# eskeetit.net
KiCad netlist of a schematic drawn in EAGLE
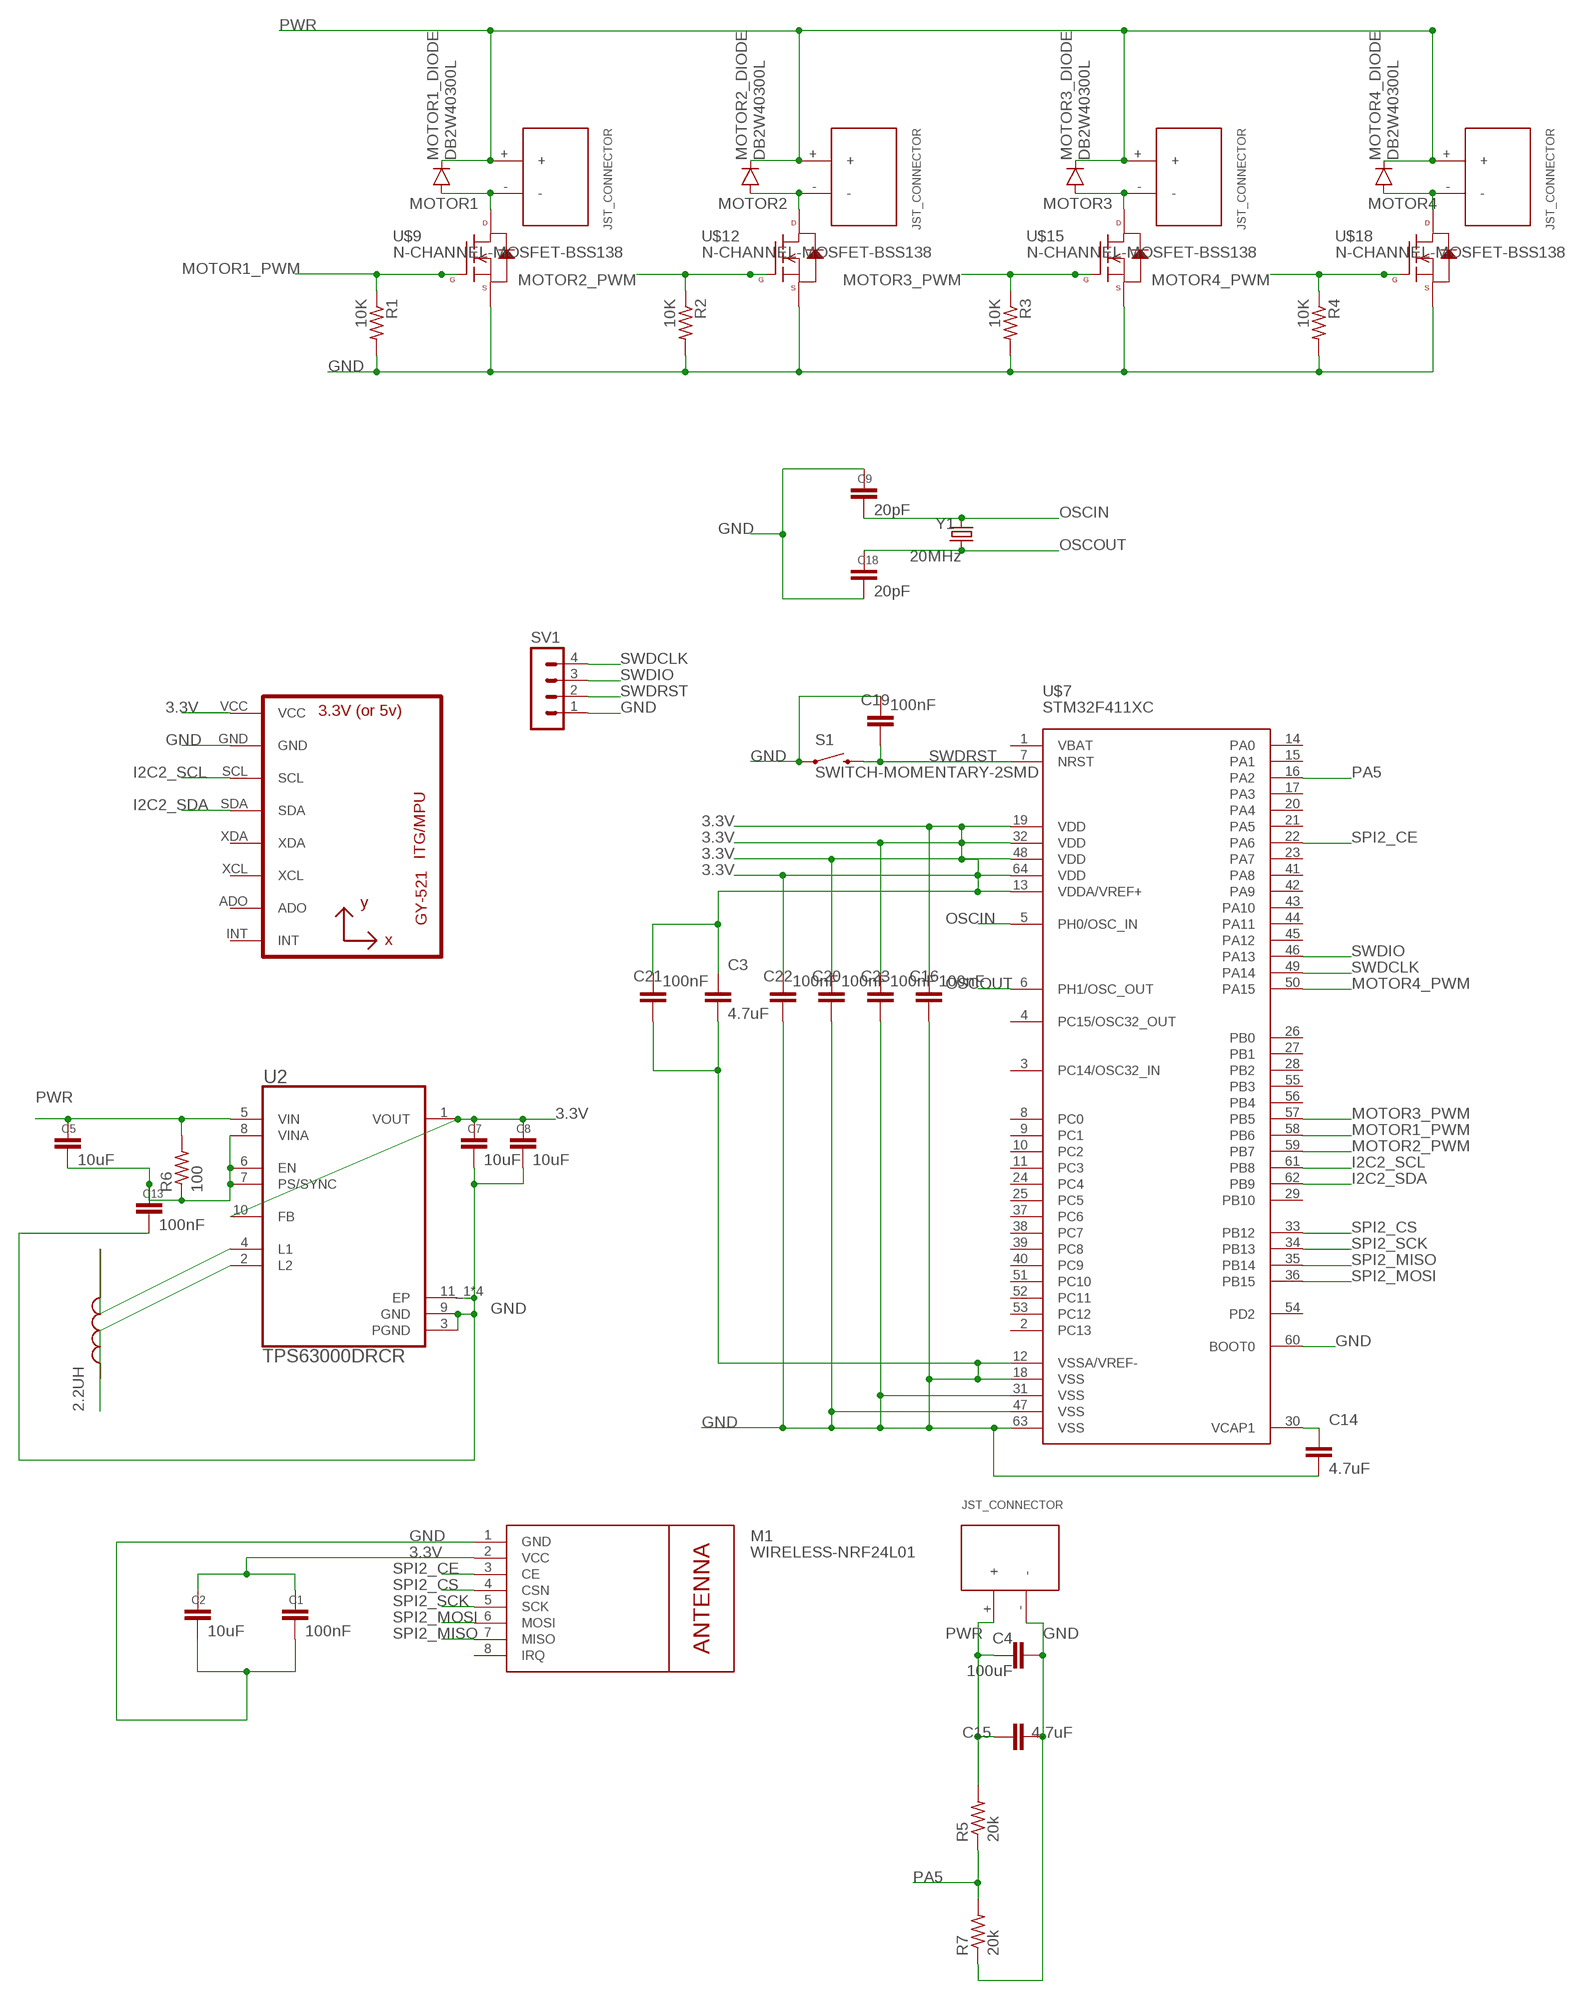
[diagram p0: schematic, sheet 1]

(export (version "E")
  (design (tool "Eeschema 10.0.6"))
  (components
    (comp (ref "2.2UH")
      (value "2.2uH")
      (footprint "eagle-import:IND_LQH2MCN100K02L")
      (fields
        (field (name "DIGI-KEY_PART_NUMBER") "490-4046-1-ND")
        (field (name "MF") "Murata Electronics")
        (field (name "MP") "LQH2MCN100K02L")
      )
      (libsource (lib "eagle-import") (part "LQH2MCN100K02L"))
    )
    (comp (ref "C1")
      (value "100nF")
      (footprint "eagle-import:RCL_C0603")
      (libsource (lib "eagle-import") (part "RCL_C-EUC0603"))
    )
    (comp (ref "C2")
      (value "10uF")
      (footprint "eagle-import:RCL_C0603")
      (libsource (lib "eagle-import") (part "RCL_C-EUC0603"))
    )
    (comp (ref "C3")
      (value "4.7uF")
      (footprint "eagle-import:RCL_C0603")
      (libsource (lib "eagle-import") (part "RCL_C-EUC0603"))
    )
    (comp (ref "C4")
      (value "100uF")
      (footprint "eagle-import:C1206")
      (libsource (lib "eagle-import") (part "C-EUC1206"))
    )
    (comp (ref "C5")
      (value "10uF")
      (footprint "eagle-import:RCL_C0603")
      (libsource (lib "eagle-import") (part "RCL_C-EUC0603"))
    )
    (comp (ref "C7")
      (value "10uF")
      (footprint "eagle-import:RCL_C0603")
      (libsource (lib "eagle-import") (part "RCL_C-EUC0603"))
    )
    (comp (ref "C8")
      (value "10uF")
      (footprint "eagle-import:RCL_C0603")
      (libsource (lib "eagle-import") (part "RCL_C-EUC0603"))
    )
    (comp (ref "C9")
      (value "20pF")
      (footprint "eagle-import:RCL_C0603")
      (libsource (lib "eagle-import") (part "RCL_C-EUC0603"))
    )
    (comp (ref "C13")
      (value "100nF")
      (footprint "eagle-import:RCL_C0603")
      (libsource (lib "eagle-import") (part "RCL_C-EUC0603"))
    )
    (comp (ref "C14")
      (value "4.7uF")
      (footprint "eagle-import:RCL_C0603")
      (libsource (lib "eagle-import") (part "RCL_C-EUC0603"))
    )
    (comp (ref "C15")
      (value "4.7uF")
      (footprint "eagle-import:RCL_C0603")
      (libsource (lib "eagle-import") (part "RCL_C-EUC0603"))
    )
    (comp (ref "C16")
      (value "100nF")
      (footprint "eagle-import:RCL_C0603")
      (libsource (lib "eagle-import") (part "RCL_C-EUC0603"))
    )
    (comp (ref "C18")
      (value "20pF")
      (footprint "eagle-import:RCL_C0603")
      (libsource (lib "eagle-import") (part "RCL_C-EUC0603"))
    )
    (comp (ref "C19")
      (value "100nF")
      (footprint "eagle-import:RCL_C0603")
      (libsource (lib "eagle-import") (part "RCL_C-EUC0603"))
    )
    (comp (ref "C20")
      (value "100nF")
      (footprint "eagle-import:RCL_C0603")
      (libsource (lib "eagle-import") (part "RCL_C-EUC0603"))
    )
    (comp (ref "C21")
      (value "100nF")
      (footprint "eagle-import:RCL_C0603")
      (libsource (lib "eagle-import") (part "RCL_C-EUC0603"))
    )
    (comp (ref "C22")
      (value "100nF")
      (footprint "eagle-import:RCL_C0603")
      (libsource (lib "eagle-import") (part "RCL_C-EUC0603"))
    )
    (comp (ref "C23")
      (value "100nF")
      (footprint "eagle-import:RCL_C0603")
      (libsource (lib "eagle-import") (part "RCL_C-EUC0603"))
    )
    (comp (ref "M1")
      (value "WIRELESS-NRF24L01")
      (footprint "eagle-import:WIRELESS-NRF24L01")
      (libsource (lib "eagle-import") (part "WIRELESS-NRF24L01"))
    )
    (comp (ref "MOTOR1")
      (value "JST_CONNECTOR_FEMALE")
      (footprint "eagle-import:JST_CONNECTOR_FEMALE")
      (libsource (lib "eagle-import") (part "JST_CONNECTOR_FEMALE"))
    )
    (comp (ref "MOTOR1_DIODE")
      (value "DB2W40300L")
      (footprint "eagle-import:MINI2-F3-B")
      (libsource (lib "eagle-import") (part "DB2W40300L"))
    )
    (comp (ref "MOTOR2_DIODE")
      (value "DB2W40300L")
      (footprint "eagle-import:MINI2-F3-B")
      (libsource (lib "eagle-import") (part "DB2W40300L"))
    )
    (comp (ref "MOTOR3_DIODE")
      (value "DB2W40300L")
      (footprint "eagle-import:MINI2-F3-B")
      (libsource (lib "eagle-import") (part "DB2W40300L"))
    )
    (comp (ref "MOTOR4_DIODE")
      (value "DB2W40300L")
      (footprint "eagle-import:MINI2-F3-B")
      (libsource (lib "eagle-import") (part "DB2W40300L"))
    )
    (comp (ref "R1")
      (value "10K")
      (footprint "eagle-import:R0603")
      (libsource (lib "eagle-import") (part "R-US_R0603"))
    )
    (comp (ref "R2")
      (value "10K")
      (footprint "eagle-import:R0603")
      (libsource (lib "eagle-import") (part "R-US_R0603"))
    )
    (comp (ref "R3")
      (value "10K")
      (footprint "eagle-import:R0603")
      (libsource (lib "eagle-import") (part "R-US_R0603"))
    )
    (comp (ref "R4")
      (value "10K")
      (footprint "eagle-import:R0603")
      (libsource (lib "eagle-import") (part "R-US_R0603"))
    )
    (comp (ref "R5")
      (value "20k")
      (footprint "eagle-import:R0603")
      (libsource (lib "eagle-import") (part "R-US_R0603"))
    )
    (comp (ref "R6")
      (value "100")
      (footprint "eagle-import:R0603")
      (libsource (lib "eagle-import") (part "R-US_R0603"))
    )
    (comp (ref "R7")
      (value "20k")
      (footprint "eagle-import:R0603")
      (libsource (lib "eagle-import") (part "R-US_R0603"))
    )
    (comp (ref "S1")
      (value "SWITCH-MOMENTARY-2SMD")
      (footprint "eagle-import:TACTILE-SWITCH-SMD")
      (libsource (lib "eagle-import") (part "SWITCH-MOMENTARY-2SMD"))
    )
    (comp (ref "SV1")
      (value "MA04-1")
      (footprint "eagle-import:MA04-1")
      (libsource (lib "eagle-import") (part "MA04-1"))
    )
    (comp (ref "U$1")
      (value "JST_CONNECTOR_FEMALE")
      (footprint "eagle-import:JST_CONNECTOR_FEMALE")
      (libsource (lib "eagle-import") (part "JST_CONNECTOR_FEMALE"))
    )
    (comp (ref "U$7")
      (value "STM32F411XC")
      (footprint "eagle-import:LQFP64")
      (libsource (lib "eagle-import") (part "STM32F411XC"))
    )
    (comp (ref "U$9")
      (value "N-CHANNEL-MOSFET-BSS138")
      (footprint "eagle-import:SOT23-3")
      (libsource (lib "eagle-import") (part "N-CHANNEL-MOSFET-BSS138"))
    )
    (comp (ref "U$11")
      (value "JST_CONNECTOR_FEMALE")
      (footprint "eagle-import:JST_CONNECTOR_FEMALE")
      (libsource (lib "eagle-import") (part "JST_CONNECTOR_FEMALE"))
    )
    (comp (ref "U$12")
      (value "N-CHANNEL-MOSFET-BSS138")
      (footprint "eagle-import:SOT23-3")
      (libsource (lib "eagle-import") (part "N-CHANNEL-MOSFET-BSS138"))
    )
    (comp (ref "U$14")
      (value "JST_CONNECTOR_FEMALE")
      (footprint "eagle-import:JST_CONNECTOR_FEMALE")
      (libsource (lib "eagle-import") (part "JST_CONNECTOR_FEMALE"))
    )
    (comp (ref "U$15")
      (value "N-CHANNEL-MOSFET-BSS138")
      (footprint "eagle-import:SOT23-3")
      (libsource (lib "eagle-import") (part "N-CHANNEL-MOSFET-BSS138"))
    )
    (comp (ref "U$17")
      (value "JST_CONNECTOR_FEMALE")
      (footprint "eagle-import:JST_CONNECTOR_FEMALE")
      (libsource (lib "eagle-import") (part "JST_CONNECTOR_FEMALE"))
    )
    (comp (ref "U$18")
      (value "N-CHANNEL-MOSFET-BSS138")
      (footprint "eagle-import:SOT23-3")
      (libsource (lib "eagle-import") (part "N-CHANNEL-MOSFET-BSS138"))
    )
    (comp (ref "U1")
      (value "GY-521MPU6050")
      (footprint "eagle-import:GY-521")
      (libsource (lib "eagle-import") (part "GY-521MPU6050"))
    )
    (comp (ref "U2")
      (value "TPS63000DRCR")
      (footprint "eagle-import:CONV_TPS63000DRCR")
      (fields (field (name "DIGI-KEY_PART_NUMBER") "296-19641-1-ND") (field (name "MF") "Texas Instruments"))
      (libsource (lib "eagle-import") (part "TPS63000DRCR"))
    )
    (comp (ref "Y1")
      (value "20MHz")
      (footprint "eagle-import:HC49US")
      (libsource (lib "eagle-import") (part "CRYSTALHC49US"))
    )
  )
  (nets
    (net (code "1") (name "/3.3V") (class "Default")
      (node (ref "C1") (pin "1") (pinfunction "1_1") (pintype "passive"))
      (node (ref "C16") (pin "1") (pinfunction "1_1") (pintype "passive"))
      (node (ref "C2") (pin "1") (pinfunction "1_1") (pintype "passive"))
      (node (ref "C20") (pin "1") (pinfunction "1_1") (pintype "passive"))
      (node (ref "C21") (pin "1") (pinfunction "1_1") (pintype "passive"))
      (node (ref "C22") (pin "1") (pinfunction "1_1") (pintype "passive"))
      (node (ref "C23") (pin "1") (pinfunction "1_1") (pintype "passive"))
      (node (ref "C3") (pin "1") (pinfunction "1_1") (pintype "passive"))
      (node (ref "C7") (pin "1") (pinfunction "1_1") (pintype "passive"))
      (node (ref "C8") (pin "1") (pinfunction "1_1") (pintype "passive"))
      (node (ref "M1") (pin "2") (pinfunction "VCC_2") (pintype "power_in"))
      (node (ref "U$7") (pin "13") (pinfunction "VDDA/VREF+_13") (pintype "bidirectional"))
      (node (ref "U$7") (pin "19") (pinfunction "VDD_19") (pintype "bidirectional"))
      (node (ref "U$7") (pin "32") (pinfunction "VDD_32") (pintype "bidirectional"))
      (node (ref "U$7") (pin "48") (pinfunction "VDD_48") (pintype "bidirectional"))
      (node (ref "U$7") (pin "64") (pinfunction "VDD_64") (pintype "bidirectional"))
      (node (ref "U1") (pin "VCC") (pinfunction "VCC_VCC") (pintype "bidirectional"))
      (node (ref "U2") (pin "1") (pinfunction "VOUT_1") (pintype "output"))
      (node (ref "U2") (pin "10") (pinfunction "FB_10") (pintype "input"))
    )
    (net (code "2") (name "/GND") (class "Default")
      (node (ref "C1") (pin "2") (pinfunction "2_2") (pintype "passive"))
      (node (ref "C13") (pin "2") (pinfunction "2_2") (pintype "passive"))
      (node (ref "C14") (pin "2") (pinfunction "2_2") (pintype "passive"))
      (node (ref "C15") (pin "2") (pinfunction "2_2") (pintype "passive"))
      (node (ref "C16") (pin "2") (pinfunction "2_2") (pintype "passive"))
      (node (ref "C18") (pin "2") (pinfunction "2_2") (pintype "passive"))
      (node (ref "C19") (pin "1") (pinfunction "1_1") (pintype "passive"))
      (node (ref "C2") (pin "2") (pinfunction "2_2") (pintype "passive"))
      (node (ref "C20") (pin "2") (pinfunction "2_2") (pintype "passive"))
      (node (ref "C21") (pin "2") (pinfunction "2_2") (pintype "passive"))
      (node (ref "C22") (pin "2") (pinfunction "2_2") (pintype "passive"))
      (node (ref "C23") (pin "2") (pinfunction "2_2") (pintype "passive"))
      (node (ref "C3") (pin "2") (pinfunction "2_2") (pintype "passive"))
      (node (ref "C4") (pin "1") (pinfunction "1_1") (pintype "passive"))
      (node (ref "C7") (pin "2") (pinfunction "2_2") (pintype "passive"))
      (node (ref "C8") (pin "2") (pinfunction "2_2") (pintype "passive"))
      (node (ref "C9") (pin "1") (pinfunction "1_1") (pintype "passive"))
      (node (ref "M1") (pin "1") (pinfunction "GND_1") (pintype "power_in"))
      (node (ref "R1") (pin "2") (pinfunction "2_2") (pintype "passive"))
      (node (ref "R2") (pin "2") (pinfunction "2_2") (pintype "passive"))
      (node (ref "R3") (pin "2") (pinfunction "2_2") (pintype "passive"))
      (node (ref "R4") (pin "2") (pinfunction "2_2") (pintype "passive"))
      (node (ref "R7") (pin "1") (pinfunction "1_1") (pintype "passive"))
      (node (ref "S1") (pin "1") (pinfunction "1_1") (pintype "passive"))
      (node (ref "SV1") (pin "1") (pinfunction "1_1") (pintype "passive"))
      (node (ref "U$1") (pin "-") (pinfunction "-_-") (pintype "bidirectional"))
      (node (ref "U$12") (pin "2") (pinfunction "S_2") (pintype "passive"))
      (node (ref "U$15") (pin "2") (pinfunction "S_2") (pintype "passive"))
      (node (ref "U$18") (pin "2") (pinfunction "S_2") (pintype "passive"))
      (node (ref "U$7") (pin "12") (pinfunction "VSSA/VREF-_12") (pintype "bidirectional"))
      (node (ref "U$7") (pin "18") (pinfunction "VSS_18") (pintype "bidirectional"))
      (node (ref "U$7") (pin "31") (pinfunction "VSS_31") (pintype "bidirectional"))
      (node (ref "U$7") (pin "47") (pinfunction "VSS_47") (pintype "bidirectional"))
      (node (ref "U$7") (pin "60") (pinfunction "BOOT0_60") (pintype "bidirectional"))
      (node (ref "U$7") (pin "63") (pinfunction "VSS_63") (pintype "bidirectional"))
      (node (ref "U$9") (pin "2") (pinfunction "S_2") (pintype "passive"))
      (node (ref "U1") (pin "GND") (pinfunction "GND_GND") (pintype "bidirectional"))
      (node (ref "U2") (pin "11_1") (pinfunction "EP_11_1") (pintype "power_in"))
      (node (ref "U2") (pin "11_2") (pinfunction "EP_11_2") (pintype "power_in"))
      (node (ref "U2") (pin "11_3") (pinfunction "EP_11_3") (pintype "power_in"))
      (node (ref "U2") (pin "11_4") (pinfunction "EP_11_4") (pintype "power_in"))
      (node (ref "U2") (pin "3") (pinfunction "PGND_3") (pintype "power_in"))
      (node (ref "U2") (pin "9") (pinfunction "GND_9") (pintype "power_in"))
    )
    (net (code "3") (name "/I2C2_SCL") (class "Default")
      (node (ref "U$7") (pin "61") (pinfunction "PB8_61") (pintype "bidirectional"))
      (node (ref "U1") (pin "SCL") (pinfunction "SCL_SCL") (pintype "bidirectional"))
    )
    (net (code "4") (name "/I2C2_SDA") (class "Default")
      (node (ref "U$7") (pin "62") (pinfunction "PB9_62") (pintype "bidirectional"))
      (node (ref "U1") (pin "SDA") (pinfunction "SDA_SDA") (pintype "bidirectional"))
    )
    (net (code "5") (name "/MOTOR1") (class "Default")
      (node (ref "MOTOR1") (pin "-") (pinfunction "-_-") (pintype "bidirectional"))
      (node (ref "MOTOR1_DIODE") (pin "POS") (pinfunction "PPIN_POS") (pintype "passive"))
      (node (ref "U$9") (pin "3") (pinfunction "D_3") (pintype "passive"))
    )
    (net (code "6") (name "/MOTOR1_PWM") (class "Default")
      (node (ref "R1") (pin "1") (pinfunction "1_1") (pintype "passive"))
      (node (ref "U$7") (pin "58") (pinfunction "PB6_58") (pintype "bidirectional"))
      (node (ref "U$9") (pin "1") (pinfunction "G_1") (pintype "passive"))
    )
    (net (code "7") (name "/MOTOR2") (class "Default")
      (node (ref "MOTOR2_DIODE") (pin "POS") (pinfunction "PPIN_POS") (pintype "passive"))
      (node (ref "U$11") (pin "-") (pinfunction "-_-") (pintype "bidirectional"))
      (node (ref "U$12") (pin "3") (pinfunction "D_3") (pintype "passive"))
    )
    (net (code "8") (name "/MOTOR2_PWM") (class "Default")
      (node (ref "R2") (pin "1") (pinfunction "1_1") (pintype "passive"))
      (node (ref "U$12") (pin "1") (pinfunction "G_1") (pintype "passive"))
      (node (ref "U$7") (pin "59") (pinfunction "PB7_59") (pintype "bidirectional"))
    )
    (net (code "9") (name "/MOTOR3") (class "Default")
      (node (ref "MOTOR3_DIODE") (pin "POS") (pinfunction "PPIN_POS") (pintype "passive"))
      (node (ref "U$14") (pin "-") (pinfunction "-_-") (pintype "bidirectional"))
      (node (ref "U$15") (pin "3") (pinfunction "D_3") (pintype "passive"))
    )
    (net (code "10") (name "/MOTOR3_PWM") (class "Default")
      (node (ref "R3") (pin "1") (pinfunction "1_1") (pintype "passive"))
      (node (ref "U$15") (pin "1") (pinfunction "G_1") (pintype "passive"))
      (node (ref "U$7") (pin "57") (pinfunction "PB5_57") (pintype "bidirectional"))
    )
    (net (code "11") (name "/MOTOR4") (class "Default")
      (node (ref "MOTOR4_DIODE") (pin "POS") (pinfunction "PPIN_POS") (pintype "passive"))
      (node (ref "U$17") (pin "-") (pinfunction "-_-") (pintype "bidirectional"))
      (node (ref "U$18") (pin "3") (pinfunction "D_3") (pintype "passive"))
    )
    (net (code "12") (name "/MOTOR4_PWM") (class "Default")
      (node (ref "R4") (pin "1") (pinfunction "1_1") (pintype "passive"))
      (node (ref "U$18") (pin "1") (pinfunction "G_1") (pintype "passive"))
      (node (ref "U$7") (pin "50") (pinfunction "PA15_50") (pintype "bidirectional"))
    )
    (net (code "13") (name "/OSCIN") (class "Default")
      (node (ref "C9") (pin "2") (pinfunction "2_2") (pintype "passive"))
      (node (ref "U$7") (pin "5") (pinfunction "PH0/OSC_IN_5") (pintype "bidirectional"))
      (node (ref "Y1") (pin "2") (pinfunction "2_2") (pintype "passive"))
    )
    (net (code "14") (name "/OSCOUT") (class "Default")
      (node (ref "C18") (pin "1") (pinfunction "1_1") (pintype "passive"))
      (node (ref "U$7") (pin "6") (pinfunction "PH1/OSC_OUT_6") (pintype "bidirectional"))
      (node (ref "Y1") (pin "1") (pinfunction "1_1") (pintype "passive"))
    )
    (net (code "15") (name "/PA5") (class "Default")
      (node (ref "R5") (pin "1") (pinfunction "1_1") (pintype "passive"))
      (node (ref "R7") (pin "2") (pinfunction "2_2") (pintype "passive"))
      (node (ref "U$7") (pin "16") (pinfunction "PA2_16") (pintype "bidirectional"))
    )
    (net (code "16") (name "/PWR") (class "Default")
      (node (ref "C15") (pin "1") (pinfunction "1_1") (pintype "passive"))
      (node (ref "C4") (pin "2") (pinfunction "2_2") (pintype "passive"))
      (node (ref "C5") (pin "1") (pinfunction "1_1") (pintype "passive"))
      (node (ref "MOTOR1") (pin "+") (pinfunction "+_+") (pintype "bidirectional"))
      (node (ref "MOTOR1_DIODE") (pin "NEG") (pinfunction "GPIN_NEG") (pintype "passive"))
      (node (ref "MOTOR2_DIODE") (pin "NEG") (pinfunction "GPIN_NEG") (pintype "passive"))
      (node (ref "MOTOR3_DIODE") (pin "NEG") (pinfunction "GPIN_NEG") (pintype "passive"))
      (node (ref "MOTOR4_DIODE") (pin "NEG") (pinfunction "GPIN_NEG") (pintype "passive"))
      (node (ref "R5") (pin "2") (pinfunction "2_2") (pintype "passive"))
      (node (ref "R6") (pin "2") (pinfunction "2_2") (pintype "passive"))
      (node (ref "U$1") (pin "+") (pinfunction "+_+") (pintype "bidirectional"))
      (node (ref "U$11") (pin "+") (pinfunction "+_+") (pintype "bidirectional"))
      (node (ref "U$14") (pin "+") (pinfunction "+_+") (pintype "bidirectional"))
      (node (ref "U$17") (pin "+") (pinfunction "+_+") (pintype "bidirectional"))
      (node (ref "U2") (pin "5") (pinfunction "VIN_5") (pintype "input"))
    )
    (net (code "17") (name "/SPI2_CE") (class "Default")
      (node (ref "M1") (pin "3") (pinfunction "CE_3") (pintype "bidirectional"))
      (node (ref "U$7") (pin "22") (pinfunction "PA6_22") (pintype "bidirectional"))
    )
    (net (code "18") (name "/SPI2_CS") (class "Default")
      (node (ref "M1") (pin "4") (pinfunction "CSN_4") (pintype "bidirectional"))
      (node (ref "U$7") (pin "33") (pinfunction "PB12_33") (pintype "bidirectional"))
    )
    (net (code "19") (name "/SPI2_MISO") (class "Default")
      (node (ref "M1") (pin "7") (pinfunction "MISO_7") (pintype "bidirectional"))
      (node (ref "U$7") (pin "35") (pinfunction "PB14_35") (pintype "bidirectional"))
    )
    (net (code "20") (name "/SPI2_MOSI") (class "Default")
      (node (ref "M1") (pin "6") (pinfunction "MOSI_6") (pintype "bidirectional"))
      (node (ref "U$7") (pin "36") (pinfunction "PB15_36") (pintype "bidirectional"))
    )
    (net (code "21") (name "/SPI2_SCK") (class "Default")
      (node (ref "M1") (pin "5") (pinfunction "SCK_5") (pintype "bidirectional"))
      (node (ref "U$7") (pin "34") (pinfunction "PB13_34") (pintype "bidirectional"))
    )
    (net (code "22") (name "/SWDCLK") (class "Default")
      (node (ref "SV1") (pin "4") (pinfunction "4_4") (pintype "passive"))
      (node (ref "U$7") (pin "49") (pinfunction "PA14_49") (pintype "bidirectional"))
    )
    (net (code "23") (name "/SWDIO") (class "Default")
      (node (ref "SV1") (pin "3") (pinfunction "3_3") (pintype "passive"))
      (node (ref "U$7") (pin "46") (pinfunction "PA13_46") (pintype "bidirectional"))
    )
    (net (code "24") (name "/SWDRST") (class "Default")
      (node (ref "C19") (pin "2") (pinfunction "2_2") (pintype "passive"))
      (node (ref "S1") (pin "3") (pinfunction "2_3") (pintype "passive"))
      (node (ref "SV1") (pin "2") (pinfunction "2_2") (pintype "passive"))
      (node (ref "U$7") (pin "7") (pinfunction "NRST_7") (pintype "bidirectional"))
    )
    (net (code "25") (name "Net-(U$7-VCAP1)") (class "Default")
      (node (ref "C14") (pin "1") (pinfunction "1_1") (pintype "passive"))
      (node (ref "U$7") (pin "30") (pinfunction "VCAP1_30") (pintype "bidirectional"))
    )
    (net (code "26") (name "Net-(U2-EN)") (class "Default")
      (node (ref "C13") (pin "1") (pinfunction "1_1") (pintype "passive"))
      (node (ref "C5") (pin "2") (pinfunction "2_2") (pintype "passive"))
      (node (ref "R6") (pin "1") (pinfunction "1_1") (pintype "passive"))
      (node (ref "U2") (pin "6") (pinfunction "EN_6") (pintype "input"))
      (node (ref "U2") (pin "7") (pinfunction "PS/SYNC_7") (pintype "input"))
      (node (ref "U2") (pin "8") (pinfunction "VINA_8") (pintype "input"))
    )
    (net (code "27") (name "Net-(U2-L1)") (class "Default")
      (node (ref "2.2UH") (pin "2") (pinfunction "2_2") (pintype "passive"))
      (node (ref "U2") (pin "4") (pinfunction "L1_4") (pintype "input"))
    )
    (net (code "28") (name "Net-(U2-L2)") (class "Default")
      (node (ref "2.2UH") (pin "1") (pinfunction "1_1") (pintype "passive"))
      (node (ref "U2") (pin "2") (pinfunction "L2_2") (pintype "input"))
    )
    (net (code "29") (name "unconnected-(M1-IRQ-Pad8)") (class "Default")
      (node (ref "M1") (pin "8") (pinfunction "IRQ_8") (pintype "bidirectional"))
    )
    (net (code "30") (name "unconnected-(U$7-PA0-Pad14)") (class "Default")
      (node (ref "U$7") (pin "14") (pinfunction "PA0_14") (pintype "bidirectional"))
    )
    (net (code "31") (name "unconnected-(U$7-PA1-Pad15)") (class "Default")
      (node (ref "U$7") (pin "15") (pinfunction "PA1_15") (pintype "bidirectional"))
    )
    (net (code "32") (name "unconnected-(U$7-PA3-Pad17)") (class "Default")
      (node (ref "U$7") (pin "17") (pinfunction "PA3_17") (pintype "bidirectional"))
    )
    (net (code "33") (name "unconnected-(U$7-PA4-Pad20)") (class "Default")
      (node (ref "U$7") (pin "20") (pinfunction "PA4_20") (pintype "bidirectional"))
    )
    (net (code "34") (name "unconnected-(U$7-PA5-Pad21)") (class "Default")
      (node (ref "U$7") (pin "21") (pinfunction "PA5_21") (pintype "bidirectional"))
    )
    (net (code "35") (name "unconnected-(U$7-PA7-Pad23)") (class "Default")
      (node (ref "U$7") (pin "23") (pinfunction "PA7_23") (pintype "bidirectional"))
    )
    (net (code "36") (name "unconnected-(U$7-PA8-Pad41)") (class "Default")
      (node (ref "U$7") (pin "41") (pinfunction "PA8_41") (pintype "bidirectional"))
    )
    (net (code "37") (name "unconnected-(U$7-PA9-Pad42)") (class "Default")
      (node (ref "U$7") (pin "42") (pinfunction "PA9_42") (pintype "bidirectional"))
    )
    (net (code "38") (name "unconnected-(U$7-PA10-Pad43)") (class "Default")
      (node (ref "U$7") (pin "43") (pinfunction "PA10_43") (pintype "bidirectional"))
    )
    (net (code "39") (name "unconnected-(U$7-PA11-Pad44)") (class "Default")
      (node (ref "U$7") (pin "44") (pinfunction "PA11_44") (pintype "bidirectional"))
    )
    (net (code "40") (name "unconnected-(U$7-PA12-Pad45)") (class "Default")
      (node (ref "U$7") (pin "45") (pinfunction "PA12_45") (pintype "bidirectional"))
    )
    (net (code "41") (name "unconnected-(U$7-PB0-Pad26)") (class "Default")
      (node (ref "U$7") (pin "26") (pinfunction "PB0_26") (pintype "bidirectional"))
    )
    (net (code "42") (name "unconnected-(U$7-PB1-Pad27)") (class "Default")
      (node (ref "U$7") (pin "27") (pinfunction "PB1_27") (pintype "bidirectional"))
    )
    (net (code "43") (name "unconnected-(U$7-PB2-Pad28)") (class "Default")
      (node (ref "U$7") (pin "28") (pinfunction "PB2_28") (pintype "bidirectional"))
    )
    (net (code "44") (name "unconnected-(U$7-PB3-Pad55)") (class "Default")
      (node (ref "U$7") (pin "55") (pinfunction "PB3_55") (pintype "bidirectional"))
    )
    (net (code "45") (name "unconnected-(U$7-PB4-Pad56)") (class "Default")
      (node (ref "U$7") (pin "56") (pinfunction "PB4_56") (pintype "bidirectional"))
    )
    (net (code "46") (name "unconnected-(U$7-PB10-Pad29)") (class "Default")
      (node (ref "U$7") (pin "29") (pinfunction "PB10_29") (pintype "bidirectional"))
    )
    (net (code "47") (name "unconnected-(U$7-PC0-Pad8)") (class "Default")
      (node (ref "U$7") (pin "8") (pinfunction "PC0_8") (pintype "bidirectional"))
    )
    (net (code "48") (name "unconnected-(U$7-PC1-Pad9)") (class "Default")
      (node (ref "U$7") (pin "9") (pinfunction "PC1_9") (pintype "bidirectional"))
    )
    (net (code "49") (name "unconnected-(U$7-PC2-Pad10)") (class "Default")
      (node (ref "U$7") (pin "10") (pinfunction "PC2_10") (pintype "bidirectional"))
    )
    (net (code "50") (name "unconnected-(U$7-PC3-Pad11)") (class "Default")
      (node (ref "U$7") (pin "11") (pinfunction "PC3_11") (pintype "bidirectional"))
    )
    (net (code "51") (name "unconnected-(U$7-PC4-Pad24)") (class "Default")
      (node (ref "U$7") (pin "24") (pinfunction "PC4_24") (pintype "bidirectional"))
    )
    (net (code "52") (name "unconnected-(U$7-PC5-Pad25)") (class "Default")
      (node (ref "U$7") (pin "25") (pinfunction "PC5_25") (pintype "bidirectional"))
    )
    (net (code "53") (name "unconnected-(U$7-PC6-Pad37)") (class "Default")
      (node (ref "U$7") (pin "37") (pinfunction "PC6_37") (pintype "bidirectional"))
    )
    (net (code "54") (name "unconnected-(U$7-PC7-Pad38)") (class "Default")
      (node (ref "U$7") (pin "38") (pinfunction "PC7_38") (pintype "bidirectional"))
    )
    (net (code "55") (name "unconnected-(U$7-PC8-Pad39)") (class "Default")
      (node (ref "U$7") (pin "39") (pinfunction "PC8_39") (pintype "bidirectional"))
    )
    (net (code "56") (name "unconnected-(U$7-PC9-Pad40)") (class "Default")
      (node (ref "U$7") (pin "40") (pinfunction "PC9_40") (pintype "bidirectional"))
    )
    (net (code "57") (name "unconnected-(U$7-PC10-Pad51)") (class "Default")
      (node (ref "U$7") (pin "51") (pinfunction "PC10_51") (pintype "bidirectional"))
    )
    (net (code "58") (name "unconnected-(U$7-PC11-Pad52)") (class "Default")
      (node (ref "U$7") (pin "52") (pinfunction "PC11_52") (pintype "bidirectional"))
    )
    (net (code "59") (name "unconnected-(U$7-PC12-Pad53)") (class "Default")
      (node (ref "U$7") (pin "53") (pinfunction "PC12_53") (pintype "bidirectional"))
    )
    (net (code "60") (name "unconnected-(U$7-PC13-Pad2)") (class "Default")
      (node (ref "U$7") (pin "2") (pinfunction "PC13_2") (pintype "bidirectional"))
    )
    (net (code "61") (name "unconnected-(U$7-PC14{slash}OSC32_IN-Pad3)") (class "Default")
      (node (ref "U$7") (pin "3") (pinfunction "PC14/OSC32_IN_3") (pintype "bidirectional"))
    )
    (net (code "62") (name "unconnected-(U$7-PC15{slash}OSC32_OUT-Pad4)") (class "Default")
      (node (ref "U$7") (pin "4") (pinfunction "PC15/OSC32_OUT_4") (pintype "bidirectional"))
    )
    (net (code "63") (name "unconnected-(U$7-PD2-Pad54)") (class "Default")
      (node (ref "U$7") (pin "54") (pinfunction "PD2_54") (pintype "bidirectional"))
    )
    (net (code "64") (name "unconnected-(U$7-VBAT-Pad1)") (class "Default")
      (node (ref "U$7") (pin "1") (pinfunction "VBAT_1") (pintype "bidirectional"))
    )
    (net (code "65") (name "unconnected-(U1-PadADO)") (class "Default")
      (node (ref "U1") (pin "ADO") (pinfunction "ADO_ADO") (pintype "bidirectional"))
    )
    (net (code "66") (name "unconnected-(U1-PadINT)") (class "Default")
      (node (ref "U1") (pin "INT") (pinfunction "INT_INT") (pintype "bidirectional"))
    )
    (net (code "67") (name "unconnected-(U1-PadXCL)") (class "Default")
      (node (ref "U1") (pin "XCL") (pinfunction "XCL_XCL") (pintype "bidirectional"))
    )
    (net (code "68") (name "unconnected-(U1-PadXDA)") (class "Default")
      (node (ref "U1") (pin "XDA") (pinfunction "XDA_XDA") (pintype "bidirectional"))
    )
  )
)
